# motor_control.net
KiCad netlist of a schematic drawn in Altium Designer
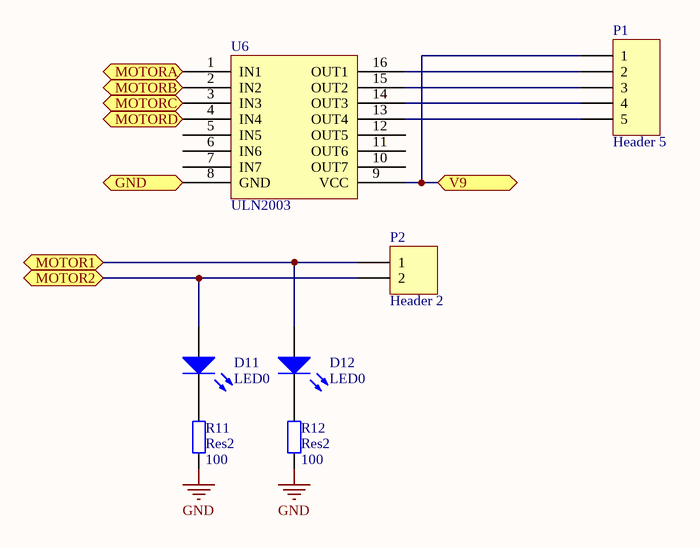
[diagram p0: motor_control.SchDoc]

(export (version "E")
  (design (tool "Eeschema 10.0.6"))
  (components
    (comp (ref "D11")
      (value "LED0")
      (footprint "1206")
      (description "Typical INFRARED GaAs LED")
      (fields (field (name "PUBLISHER") "Altium Limited"))
      (libsource (lib "Miscellaneous Devices") (part "LED0"))
    )
    (comp (ref "D12")
      (value "LED0")
      (footprint "1206")
      (description "Typical INFRARED GaAs LED")
      (fields (field (name "PUBLISHER") "Altium Limited"))
      (libsource (lib "Miscellaneous Devices") (part "LED0"))
    )
    (comp (ref "P1")
      (value "Header 5")
      (footprint "HDR1X5")
      (description "Header, 5-Pin")
      (fields (field (name "PUBLISHER") "Altium Limited"))
      (libsource (lib "Miscellaneous Connectors") (part "Header 5"))
    )
    (comp (ref "P2")
      (value "Header 2")
      (footprint "HDR1X2")
      (description "Header, 2-Pin")
      (fields (field (name "PUBLISHER") "Altium Limited"))
      (libsource (lib "Miscellaneous Connectors") (part "Header 2"))
    )
    (comp (ref "R11")
      (value "Res2")
      (footprint "0603")
      (description "Resistor")
      (fields (field (name "ALTIUM_VALUE") "100") (field (name "PUBLISHER") "Altium Limited"))
      (libsource (lib "Miscellaneous Devices") (part "Res2"))
    )
    (comp (ref "R12")
      (value "Res2")
      (footprint "0603")
      (description "Resistor")
      (fields (field (name "ALTIUM_VALUE") "100") (field (name "PUBLISHER") "Altium Limited"))
      (libsource (lib "Miscellaneous Devices") (part "Res2"))
    )
    (comp (ref "U6") (value "ULN2003") (footprint "SOP-16") (libsource (lib "mylib") (part "ULN2003")))
  )
  (nets
    (net (code "1") (name "/MOTOR1") (class "Default")
      (node (ref "D12") (pin "1") (pinfunction "A_1") (pintype "passive"))
      (node (ref "P2") (pin "1") (pinfunction "1_1") (pintype "passive"))
    )
    (net (code "2") (name "/MOTOR2") (class "Default")
      (node (ref "D11") (pin "1") (pinfunction "A_1") (pintype "passive"))
      (node (ref "P2") (pin "2") (pinfunction "2_2") (pintype "passive"))
    )
    (net (code "3") (name "/MOTORA") (class "Default")
      (node (ref "U6") (pin "1") (pinfunction "IN1_1") (pintype "passive"))
    )
    (net (code "4") (name "/MOTORB") (class "Default")
      (node (ref "U6") (pin "2") (pinfunction "IN2_2") (pintype "passive"))
    )
    (net (code "5") (name "/MOTORC") (class "Default")
      (node (ref "U6") (pin "3") (pinfunction "IN3_3") (pintype "passive"))
    )
    (net (code "6") (name "/MOTORD") (class "Default")
      (node (ref "U6") (pin "4") (pinfunction "IN4_4") (pintype "passive"))
    )
    (net (code "7") (name "/V9") (class "Default")
      (node (ref "P1") (pin "1") (pinfunction "1_1") (pintype "passive"))
      (node (ref "U6") (pin "9") (pinfunction "VCC_9") (pintype "passive"))
    )
    (net (code "8") (name "GND") (class "Default")
      (node (ref "R11") (pin "1") (pinfunction "1_1") (pintype "passive"))
      (node (ref "R12") (pin "1") (pinfunction "1_1") (pintype "passive"))
      (node (ref "U6") (pin "8") (pinfunction "GND_8") (pintype "passive"))
    )
    (net (code "9") (name "Net-(D11-K)") (class "Default")
      (node (ref "D11") (pin "2") (pinfunction "K_2") (pintype "passive"))
      (node (ref "R11") (pin "2") (pinfunction "2_2") (pintype "passive"))
    )
    (net (code "10") (name "Net-(D12-K)") (class "Default")
      (node (ref "D12") (pin "2") (pinfunction "K_2") (pintype "passive"))
      (node (ref "R12") (pin "2") (pinfunction "2_2") (pintype "passive"))
    )
    (net (code "11") (name "Net-(U6-OUT1)") (class "Default")
      (node (ref "P1") (pin "2") (pinfunction "2_2") (pintype "passive"))
      (node (ref "U6") (pin "16") (pinfunction "OUT1_16") (pintype "passive"))
    )
    (net (code "12") (name "Net-(U6-OUT2)") (class "Default")
      (node (ref "P1") (pin "3") (pinfunction "3_3") (pintype "passive"))
      (node (ref "U6") (pin "15") (pinfunction "OUT2_15") (pintype "passive"))
    )
    (net (code "13") (name "Net-(U6-OUT3)") (class "Default")
      (node (ref "P1") (pin "4") (pinfunction "4_4") (pintype "passive"))
      (node (ref "U6") (pin "14") (pinfunction "OUT3_14") (pintype "passive"))
    )
    (net (code "14") (name "Net-(U6-OUT4)") (class "Default")
      (node (ref "P1") (pin "5") (pinfunction "5_5") (pintype "passive"))
      (node (ref "U6") (pin "13") (pinfunction "OUT4_13") (pintype "passive"))
    )
    (net (code "15") (name "unconnected-(U6-IN5-Pad5)") (class "Default")
      (node (ref "U6") (pin "5") (pinfunction "IN5_5") (pintype "passive"))
    )
    (net (code "16") (name "unconnected-(U6-IN6-Pad6)") (class "Default")
      (node (ref "U6") (pin "6") (pinfunction "IN6_6") (pintype "passive"))
    )
    (net (code "17") (name "unconnected-(U6-IN7-Pad7)") (class "Default")
      (node (ref "U6") (pin "7") (pinfunction "IN7_7") (pintype "passive"))
    )
    (net (code "18") (name "unconnected-(U6-OUT5-Pad12)") (class "Default")
      (node (ref "U6") (pin "12") (pinfunction "OUT5_12") (pintype "passive"))
    )
    (net (code "19") (name "unconnected-(U6-OUT6-Pad11)") (class "Default")
      (node (ref "U6") (pin "11") (pinfunction "OUT6_11") (pintype "passive"))
    )
    (net (code "20") (name "unconnected-(U6-OUT7-Pad10)") (class "Default")
      (node (ref "U6") (pin "10") (pinfunction "OUT7_10") (pintype "passive"))
    )
  )
)
